# Sheet1.net
KiCad netlist of a schematic drawn in Altium Designer
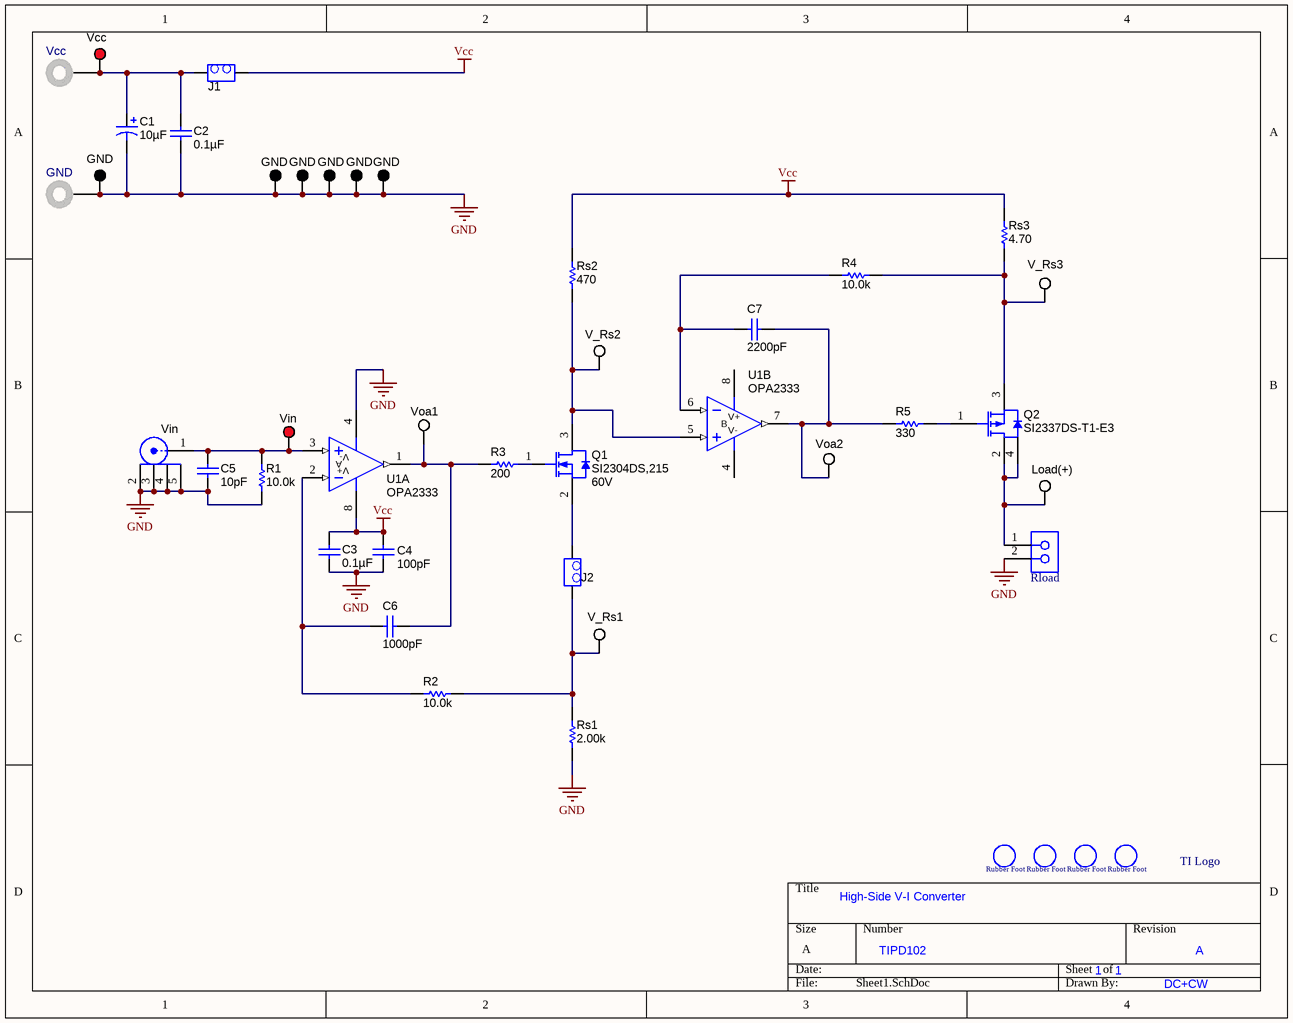
[diagram p0: Sheet1.SchDoc]

(export (version "E")
  (design (tool "Eeschema 10.0.6"))
  (components
    (comp (ref "C1")
      (value "TPSE106K050R0400")
      (footprint "7343-43")
      (description "CAP, TANT, 10uF, 50V, +/-10%, 0.4 ohm, 7343-43 SMD")
      (fields
        (field (name "VALUEDISPLAYED") "10µF")
        (field (name "MANUFACTURER") "AVX")
        (field (name "PUBLISHER") "Texas Instruments")
      )
      (libsource (lib "Capacitor_Tantalum") (part "TPSE106K050R0400"))
    )
    (comp (ref "C2")
      (value "GRM188R72A104KA35D")
      (footprint "0603")
      (description "CAP, CERM, 0.1uF, 100V, +/-10%, X7R, 0603")
      (fields
        (field (name "VALUEDISPLAYED") "0.1µF")
        (field (name "MANUFACTURER") "MuRata")
        (field (name "PUBLISHER") "Texas Instruments")
      )
      (libsource (lib "Capacitor_Ceramic") (part "GRM188R72A104KA35D"))
    )
    (comp (ref "C3")
      (value "GRM188R72A104KA35D")
      (footprint "0603")
      (description "CAP, CERM, 0.1uF, 100V, +/-10%, X7R, 0603")
      (fields
        (field (name "VALUEDISPLAYED") "0.1µF")
        (field (name "MANUFACTURER") "MuRata")
        (field (name "PUBLISHER") "Texas Instruments")
      )
      (libsource (lib "Capacitor_Ceramic") (part "GRM188R72A104KA35D"))
    )
    (comp (ref "C4")
      (value "C1608C0G2A101J")
      (footprint "0603")
      (description "CAP, CERM, 100pF, 100V, +/-5%, C0G/NP0, 0603")
      (fields
        (field (name "VALUEDISPLAYED") "100pF")
        (field (name "MANUFACTURER") "TDK")
        (field (name "PUBLISHER") "Texas Instruments")
      )
      (libsource (lib "Capacitor_Ceramic") (part "C1608C0G2A101J"))
    )
    (comp (ref "C5")
      (value "06035A100JAT2A")
      (footprint "0603")
      (description "CAP, CERM, 10pF, 50V, +/-5%, C0G/NP0, 0603")
      (fields
        (field (name "VALUEDISPLAYED") "10pF")
        (field (name "MANUFACTURER") "AVX")
        (field (name "PUBLISHER") "Texas Instruments")
      )
      (libsource (lib "Capacitor_Ceramic") (part "06035A100JAT2A"))
    )
    (comp (ref "C6")
      (value "06031C102JAT2A")
      (footprint "0603")
      (description "CAP, CERM, 1000pF, 100V, +/-5%, X7R, 0603")
      (fields
        (field (name "VALUEDISPLAYED") "1000pF")
        (field (name "MANUFACTURER") "AVX")
        (field (name "PUBLISHER") "Texas Instruments")
      )
      (libsource (lib "Capacitor_Ceramic") (part "06031C102JAT2A"))
    )
    (comp (ref "C7")
      (value "C1608C0G1H222J")
      (footprint "0603")
      (description "CAP, CERM, 2200pF, 50V, +/-5%, C0G/NP0, 0603")
      (fields
        (field (name "VALUEDISPLAYED") "2200pF")
        (field (name "MANUFACTURER") "TDK")
        (field (name "PUBLISHER") "Texas Instruments")
      )
      (libsource (lib "Capacitor_Ceramic") (part "C1608C0G1H222J"))
    )
    (comp (ref "F1")
      (value "~")
      (footprint "Rubber_Foot")
      (description "BUMPON CYLINDRICAL .312X.200 BLK")
      (fields (field (name "MANUFACTURER") "3M") (field (name "SYMBOLCREATOR") "use LDAP id"))
      (libsource (lib "Schlib1") (part "SJ61A1"))
    )
    (comp (ref "F2")
      (value "~")
      (footprint "Rubber_Foot")
      (description "BUMPON CYLINDRICAL .312X.200 BLK")
      (fields (field (name "MANUFACTURER") "3M") (field (name "SYMBOLCREATOR") "use LDAP id"))
      (libsource (lib "Schlib1") (part "SJ61A1"))
    )
    (comp (ref "F3")
      (value "~")
      (footprint "Rubber_Foot")
      (description "BUMPON CYLINDRICAL .312X.200 BLK")
      (fields (field (name "MANUFACTURER") "3M") (field (name "SYMBOLCREATOR") "use LDAP id"))
      (libsource (lib "Schlib1") (part "SJ61A1"))
    )
    (comp (ref "F4")
      (value "~")
      (footprint "Rubber_Foot")
      (description "BUMPON CYLINDRICAL .312X.200 BLK")
      (fields (field (name "MANUFACTURER") "3M") (field (name "SYMBOLCREATOR") "use LDAP id"))
      (libsource (lib "Schlib1") (part "SJ61A1"))
    )
    (comp (ref "GND")
      (value "575-4")
      (footprint "Keystone_575-4")
      (description "Standard Banana Jack, Uninsulated, 5.5mm")
      (fields (field (name "MANUFACTURER") "Keystone") (field (name "PUBLISHER") "National Semiconductor"))
      (libsource (lib "Connectors") (part "575-4"))
    )
    (comp (ref "H1")
      (value "Vin")
      (footprint "Johnson_142-0701-20x")
      (description "Connector, TH, SMA")
      (fields
        (field (name "PARTNUMBER") "142-0701-201")
        (field (name "MANUFACTURER") "Emerson Network Power")
        (field (name "PUBLISHER") "National Semiconductor")
      )
      (libsource (lib "Connectors") (part "142-0701-201"))
    )
    (comp (ref "J1")
      (value "TSM-102-01-T-SV")
      (description "CONN HEADER 2POS .100\" SNGL SMD")
      (fields (field (name "MANUFACTURER") "Samtec") (field (name "SYMBOLCREATOR") "Use LDAP id"))
      (libsource (lib "") (part "TSM-102-01-T-SV_1"))
    )
    (comp (ref "J2")
      (value "TSM-102-01-T-SV")
      (description "CONN HEADER 2POS .100\" SNGL SMD")
      (fields (field (name "MANUFACTURER") "Samtec") (field (name "SYMBOLCREATOR") "Use LDAP id"))
      (libsource (lib "Schlib1") (part "TSM-102-01-T-SV"))
    )
    (comp (ref "Q1")
      (value "SI2304DS,215")
      (footprint "SOT-23")
      (description "MOSFET, N-CH, 30V, 4.5A, SOT-23")
      (fields
        (field (name "ALTIUM_VALUE") "60V")
        (field (name "PARTNUMBER") "NTF2955T1G")
        (field (name "MANUFACTURER") "ON Semi")
      )
      (libsource (lib "FETs") (part "SI2316BDS-T1-E3"))
    )
    (comp (ref "Q2")
      (value "SI2337DS-T1-E3")
      (footprint "MP04A_N")
      (description "MOSFET, P-CH, -80V, -1.2A, SOT-23")
      (fields (field (name "MANUFACTURER") "Vishay-Siliconix") (field (name "PUBLISHER") "Texas Instruments"))
      (libsource (lib "FETs") (part "SI2337DS-T1-E3"))
    )
    (comp (ref "R1")
      (value "10.0k")
      (footprint "0603")
      (description "RES, 10.0k ohm, 0.1%, 0.1W, 0603")
      (fields
        (field (name "PARTNUMBER") "RG1608P-103-B-T5")
        (field (name "MANUFACTURER") "Susumu Co Ltd")
        (field (name "PUBLISHER") "Texas Instruments")
      )
      (libsource (lib "Resistor_0603") (part "RG1608P-103-B-T5"))
    )
    (comp (ref "R2")
      (value "10.0k")
      (footprint "0603")
      (description "RES, 10.0k ohm, 1%, 0.1W, 0603")
      (fields
        (field (name "PARTNUMBER") "CRCW060310K0FKEA")
        (field (name "MANUFACTURER") "Vishay-Dale")
        (field (name "PUBLISHER") "Texas Instruments")
      )
      (libsource (lib "Resistor_0603") (part "CRCW060310K0FKEA"))
    )
    (comp (ref "R3")
      (value "200")
      (footprint "0603")
      (description "RES, 200 ohm, 1%, 0.1W, 0603")
      (fields
        (field (name "PARTNUMBER") "CRCW0603200RFKEA")
        (field (name "MANUFACTURER") "Vishay-Dale")
        (field (name "PUBLISHER") "Texas Instruments")
      )
      (libsource (lib "Resistor_0603") (part "CRCW0603200RFKEA"))
    )
    (comp (ref "R4")
      (value "10.0k")
      (footprint "0603")
      (description "RES, 10.0k ohm, 1%, 0.1W, 0603")
      (fields
        (field (name "PARTNUMBER") "CRCW060310K0FKEA")
        (field (name "MANUFACTURER") "Vishay-Dale")
        (field (name "PUBLISHER") "Texas Instruments")
      )
      (libsource (lib "Resistor_0603") (part "CRCW060310K0FKEA"))
    )
    (comp (ref "R5")
      (value "330")
      (footprint "0603")
      (description "RES, 330 ohm, 1%, 0.1W, 0603")
      (fields
        (field (name "PARTNUMBER") "RC0603FR-07330RL")
        (field (name "MANUFACTURER") "Yageo America")
        (field (name "PUBLISHER") "Texas Instruments")
      )
      (libsource (lib "Resistor_0603") (part "RC0603FR-07330RL"))
    )
    (comp (ref "Rload")
      (value "1715721")
      (footprint "PhoenixContact_1715721")
      (description "Conn Term Block, 2POS, 5.08mm PCB")
      (fields
        (field (name "MANUFACTURER") "Phoenix Contact")
        (field (name "PUBLISHER") "National Semiconductor")
      )
      (libsource (lib "Connectors") (part "1715721"))
    )
    (comp (ref "Rs1")
      (value "2.00k")
      (footprint "0603")
      (description "RES, 2.00k ohm, 0.1%, 0.1W, 0603")
      (fields
        (field (name "PARTNUMBER") "RG1608P-202-B-T5")
        (field (name "MANUFACTURER") "Susumu Co Ltd")
        (field (name "PUBLISHER") "Texas Instruments")
      )
      (libsource (lib "Resistor_0603") (part "RG1608P-202-B-T5"))
    )
    (comp (ref "Rs2")
      (value "470")
      (footprint "0603")
      (description "RES 470 OHM 1/6W 0.1% 0603")
      (fields
        (field (name "PARTNUMBER") "RGH1608-2C-P-471-B")
        (field (name "MANUFACTURER") "Susumu Co Ltd")
        (field (name "PUBLISHER") "Texas Instruments")
      )
      (libsource (lib "Resistor_0603") (part "RG1608P-101-B-T5"))
    )
    (comp (ref "Rs3")
      (value "4.70")
      (footprint "0603")
      (description "RES 4.70 OHM 1/16W 0.1% 0603")
      (fields
        (field (name "PARTNUMBER") "8-1614882-3")
        (field (name "MANUFACTURER") "TE Connectivity")
        (field (name "PUBLISHER") "Texas Instruments")
      )
      (libsource (lib "Resistor_0603") (part "CRCW06031R00FKEA"))
    )
    (comp (ref "TI1")
      (value "Texas Instruments logo")
      (footprint "TI LOGO")
      (description "TI BUG")
      (libsource (lib "Schlib1") (part "TI LOGO"))
    )
    (comp (ref "TP1")
      (value "Vcc")
      (footprint "Keystone5000")
      (description "Test Point, TH, Miniature, Red")
      (fields
        (field (name "MANUFACTURER") "Keystone")
        (field (name "DIGIKEYPARTNUMBER") "5000K-ND")
        (field (name "PUBLISHER") "National Semiconductor")
      )
      (libsource (lib "Connectors") (part "5000"))
    )
    (comp (ref "TP2")
      (value "GND")
      (footprint "Keystone5001")
      (description "Test Point, TH, Miniature, Black")
      (fields
        (field (name "MANUFACTURER") "Keystone")
        (field (name "DIGIKEYPARTNUMBER") "5001K-ND")
        (field (name "PUBLISHER") "National Semiconductor")
      )
      (libsource (lib "Connectors") (part "5001"))
    )
    (comp (ref "TP3")
      (value "GND")
      (footprint "Keystone5001")
      (description "Test Point, TH, Miniature, Black")
      (fields
        (field (name "MANUFACTURER") "Keystone")
        (field (name "DIGIKEYPARTNUMBER") "5001K-ND")
        (field (name "PUBLISHER") "National Semiconductor")
      )
      (libsource (lib "Connectors") (part "5001"))
    )
    (comp (ref "TP4")
      (value "GND")
      (footprint "Keystone5001")
      (description "Test Point, TH, Miniature, Black")
      (fields
        (field (name "MANUFACTURER") "Keystone")
        (field (name "DIGIKEYPARTNUMBER") "5001K-ND")
        (field (name "PUBLISHER") "National Semiconductor")
      )
      (libsource (lib "Connectors") (part "5001"))
    )
    (comp (ref "TP5")
      (value "GND")
      (footprint "Keystone5001")
      (description "Test Point, TH, Miniature, Black")
      (fields
        (field (name "MANUFACTURER") "Keystone")
        (field (name "DIGIKEYPARTNUMBER") "5001K-ND")
        (field (name "PUBLISHER") "National Semiconductor")
      )
      (libsource (lib "Connectors") (part "5001"))
    )
    (comp (ref "TP6")
      (value "GND")
      (footprint "Keystone5001")
      (description "Test Point, TH, Miniature, Black")
      (fields
        (field (name "MANUFACTURER") "Keystone")
        (field (name "DIGIKEYPARTNUMBER") "5001K-ND")
        (field (name "PUBLISHER") "National Semiconductor")
      )
      (libsource (lib "Connectors") (part "5001"))
    )
    (comp (ref "TP7")
      (value "GND")
      (footprint "Keystone5001")
      (description "Test Point, TH, Miniature, Black")
      (fields
        (field (name "MANUFACTURER") "Keystone")
        (field (name "DIGIKEYPARTNUMBER") "5001K-ND")
        (field (name "PUBLISHER") "National Semiconductor")
      )
      (libsource (lib "Connectors") (part "5001"))
    )
    (comp (ref "TP8")
      (value "Vin")
      (footprint "Keystone5000")
      (description "Test Point, TH, Miniature, Red")
      (fields
        (field (name "MANUFACTURER") "Keystone")
        (field (name "DIGIKEYPARTNUMBER") "5000K-ND")
        (field (name "PUBLISHER") "National Semiconductor")
      )
      (libsource (lib "Connectors") (part "5000"))
    )
    (comp (ref "TP9")
      (value "Voa1")
      (footprint "Keystone5002")
      (description "Test Point, TH, Miniature, White")
      (fields
        (field (name "MANUFACTURER") "Keystone")
        (field (name "DIGIKEYPARTNUMBER") "5002K-ND")
        (field (name "PUBLISHER") "National Semiconductor")
      )
      (libsource (lib "Connectors") (part "5002"))
    )
    (comp (ref "TP10")
      (value "V_Rs2")
      (footprint "Keystone5002")
      (description "Test Point, TH, Miniature, White")
      (fields
        (field (name "MANUFACTURER") "Keystone")
        (field (name "DIGIKEYPARTNUMBER") "5002K-ND")
        (field (name "PUBLISHER") "National Semiconductor")
      )
      (libsource (lib "Connectors") (part "5002"))
    )
    (comp (ref "TP11")
      (value "V_Rs1")
      (footprint "Keystone5002")
      (description "Test Point, TH, Miniature, White")
      (fields
        (field (name "MANUFACTURER") "Keystone")
        (field (name "DIGIKEYPARTNUMBER") "5002K-ND")
        (field (name "PUBLISHER") "National Semiconductor")
      )
      (libsource (lib "Connectors") (part "5002"))
    )
    (comp (ref "TP12")
      (value "Voa2")
      (footprint "Keystone5002")
      (description "Test Point, TH, Miniature, White")
      (fields
        (field (name "MANUFACTURER") "Keystone")
        (field (name "DIGIKEYPARTNUMBER") "5002K-ND")
        (field (name "PUBLISHER") "National Semiconductor")
      )
      (libsource (lib "Connectors") (part "5002"))
    )
    (comp (ref "TP13")
      (value "V_Rs3")
      (footprint "Keystone5002")
      (description "Test Point, TH, Miniature, White")
      (fields
        (field (name "MANUFACTURER") "Keystone")
        (field (name "DIGIKEYPARTNUMBER") "5002K-ND")
        (field (name "PUBLISHER") "National Semiconductor")
      )
      (libsource (lib "Connectors") (part "5002"))
    )
    (comp (ref "TP14")
      (value "Load(+)")
      (footprint "Keystone5002")
      (description "Test Point, TH, Miniature, White")
      (fields
        (field (name "MANUFACTURER") "Keystone")
        (field (name "DIGIKEYPARTNUMBER") "5002K-ND")
        (field (name "PUBLISHER") "National Semiconductor")
      )
      (libsource (lib "Connectors") (part "5002"))
    )
    (comp (ref "U1")
      (value "OPA2333")
      (footprint "M08A_L")
      (description "17MHz Rail-to-Rail Input and Output Op Amp")
      (fields (field (name "MANUFACTURER") "Texas Instruments"))
      (libsource (lib "NSC Amplifier") (part "LM6142AIM"))
    )
    (comp (ref "Vcc")
      (value "575-4")
      (footprint "Keystone_575-4")
      (description "Standard Banana Jack, Uninsulated, 5.5mm")
      (fields (field (name "MANUFACTURER") "Keystone") (field (name "PUBLISHER") "National Semiconductor"))
      (libsource (lib "Connectors") (part "575-4"))
    )
  )
  (nets
    (net (code "1") (name "GND") (class "Default")
      (node (ref "C1") (pin "2") (pinfunction "-_2") (pintype "passive"))
      (node (ref "C2") (pin "2") (pinfunction "2_2") (pintype "passive"))
      (node (ref "C3") (pin "2") (pinfunction "2_2") (pintype "passive"))
      (node (ref "C4") (pin "2") (pinfunction "2_2") (pintype "passive"))
      (node (ref "C5") (pin "2") (pinfunction "2_2") (pintype "passive"))
      (node (ref "GND") (pin "1") (pinfunction "1_1") (pintype "passive"))
      (node (ref "H1") (pin "2") (pinfunction "2_2") (pintype "passive"))
      (node (ref "H1") (pin "3") (pinfunction "3_3") (pintype "passive"))
      (node (ref "H1") (pin "4") (pinfunction "4_4") (pintype "passive"))
      (node (ref "H1") (pin "5") (pinfunction "5_5") (pintype "passive"))
      (node (ref "R1") (pin "1") (pinfunction "1_1") (pintype "passive"))
      (node (ref "Rload") (pin "2") (pinfunction "2_2") (pintype "passive"))
      (node (ref "Rs1") (pin "1") (pinfunction "1_1") (pintype "passive"))
      (node (ref "TP2") (pin "1") (pintype "passive"))
      (node (ref "TP3") (pin "1") (pintype "passive"))
      (node (ref "TP4") (pin "1") (pintype "passive"))
      (node (ref "TP5") (pin "1") (pintype "passive"))
      (node (ref "TP6") (pin "1") (pintype "passive"))
      (node (ref "TP7") (pin "1") (pintype "passive"))
      (node (ref "U1") (pin "4") (pinfunction "V-_4") (pintype "power_in"))
    )
    (net (code "2") (name "Net-(C1-+)") (class "Default")
      (node (ref "C1") (pin "1") (pinfunction "+_1") (pintype "passive"))
      (node (ref "C2") (pin "1") (pinfunction "1_1") (pintype "passive"))
      (node (ref "J1") (pin "1") (pinfunction "1_1") (pintype "passive"))
      (node (ref "TP1") (pin "1") (pintype "passive"))
      (node (ref "Vcc") (pin "1") (pinfunction "1_1") (pintype "passive"))
    )
    (net (code "3") (name "Net-(J2-Pad2)") (class "Default")
      (node (ref "J2") (pin "2") (pinfunction "2_2") (pintype "passive"))
      (node (ref "R2") (pin "2") (pinfunction "2_2") (pintype "passive"))
      (node (ref "Rs1") (pin "2") (pinfunction "2_2") (pintype "passive"))
      (node (ref "TP11") (pin "1") (pintype "passive"))
    )
    (net (code "4") (name "Net-(Q1-D)") (class "Default")
      (node (ref "Q1") (pin "3") (pinfunction "D_3") (pintype "passive"))
      (node (ref "Rs2") (pin "1") (pinfunction "1_1") (pintype "passive"))
      (node (ref "TP10") (pin "1") (pintype "passive"))
      (node (ref "U1") (pin "5") (pinfunction "IN+_5") (pintype "input"))
    )
    (net (code "5") (name "Net-(Q1-G)") (class "Default")
      (node (ref "Q1") (pin "1") (pinfunction "G_1") (pintype "passive"))
      (node (ref "R3") (pin "2") (pinfunction "2_2") (pintype "passive"))
    )
    (net (code "6") (name "Net-(Q1-S)") (class "Default")
      (node (ref "J2") (pin "1") (pinfunction "1_1") (pintype "passive"))
      (node (ref "Q1") (pin "2") (pinfunction "S_2") (pintype "passive"))
    )
    (net (code "7") (name "Net-(Q2-D-Pad2)") (class "Default")
      (node (ref "Q2") (pin "2") (pinfunction "D_2") (pintype "passive"))
      (node (ref "Q2") (pin "4") (pinfunction "D_4") (pintype "passive"))
      (node (ref "Rload") (pin "1") (pinfunction "1_1") (pintype "passive"))
      (node (ref "TP14") (pin "1") (pintype "passive"))
    )
    (net (code "8") (name "Net-(Q2-G)") (class "Default")
      (node (ref "Q2") (pin "1") (pinfunction "G_1") (pintype "passive"))
      (node (ref "R5") (pin "2") (pinfunction "2_2") (pintype "passive"))
    )
    (net (code "9") (name "Net-(Q2-S)") (class "Default")
      (node (ref "Q2") (pin "3") (pinfunction "S_3") (pintype "passive"))
      (node (ref "R4") (pin "2") (pinfunction "2_2") (pintype "passive"))
      (node (ref "Rs3") (pin "1") (pinfunction "1_1") (pintype "passive"))
      (node (ref "TP13") (pin "1") (pintype "passive"))
    )
    (net (code "10") (name "Net-(U1A-IN+)") (class "Default")
      (node (ref "C5") (pin "1") (pinfunction "1_1") (pintype "passive"))
      (node (ref "H1") (pin "1") (pinfunction "1_1") (pintype "passive"))
      (node (ref "R1") (pin "2") (pinfunction "2_2") (pintype "passive"))
      (node (ref "TP8") (pin "1") (pintype "passive"))
      (node (ref "U1") (pin "3") (pinfunction "IN+_3") (pintype "input"))
    )
    (net (code "11") (name "Net-(U1A-IN-)") (class "Default")
      (node (ref "C6") (pin "2") (pinfunction "2_2") (pintype "passive"))
      (node (ref "R2") (pin "1") (pinfunction "1_1") (pintype "passive"))
      (node (ref "U1") (pin "2") (pinfunction "IN-_2") (pintype "input"))
    )
    (net (code "12") (name "Net-(U1A-OUT)") (class "Default")
      (node (ref "C6") (pin "1") (pinfunction "1_1") (pintype "passive"))
      (node (ref "R3") (pin "1") (pinfunction "1_1") (pintype "passive"))
      (node (ref "TP9") (pin "1") (pintype "passive"))
      (node (ref "U1") (pin "1") (pinfunction "OUT_1") (pintype "output"))
    )
    (net (code "13") (name "Net-(U1B-IN-)") (class "Default")
      (node (ref "C7") (pin "2") (pinfunction "2_2") (pintype "passive"))
      (node (ref "R4") (pin "1") (pinfunction "1_1") (pintype "passive"))
      (node (ref "U1") (pin "6") (pinfunction "IN-_6") (pintype "input"))
    )
    (net (code "14") (name "Net-(U1B-OUT)") (class "Default")
      (node (ref "C7") (pin "1") (pinfunction "1_1") (pintype "passive"))
      (node (ref "R5") (pin "1") (pinfunction "1_1") (pintype "passive"))
      (node (ref "TP12") (pin "1") (pintype "passive"))
      (node (ref "U1") (pin "7") (pinfunction "OUT_7") (pintype "output"))
    )
    (net (code "15") (name "Vcc") (class "Default")
      (node (ref "C3") (pin "1") (pinfunction "1_1") (pintype "passive"))
      (node (ref "C4") (pin "1") (pinfunction "1_1") (pintype "passive"))
      (node (ref "J1") (pin "2") (pinfunction "2_2") (pintype "passive"))
      (node (ref "Rs2") (pin "2") (pinfunction "2_2") (pintype "passive"))
      (node (ref "Rs3") (pin "2") (pinfunction "2_2") (pintype "passive"))
      (node (ref "U1") (pin "8") (pinfunction "V+_8") (pintype "power_in"))
    )
    (net (code "16") (name "unconnected-(U1B-V+-Pad8)") (class "Default")
      (node (ref "U1") (pin "8") (pinfunction "V+_8") (pintype "power_in"))
    )
    (net (code "17") (name "unconnected-(U1B-V--Pad4)") (class "Default")
      (node (ref "U1") (pin "4") (pinfunction "V-_4") (pintype "power_in"))
    )
  )
)
